# woochi.net
KiCad netlist of a schematic drawn in EAGLE
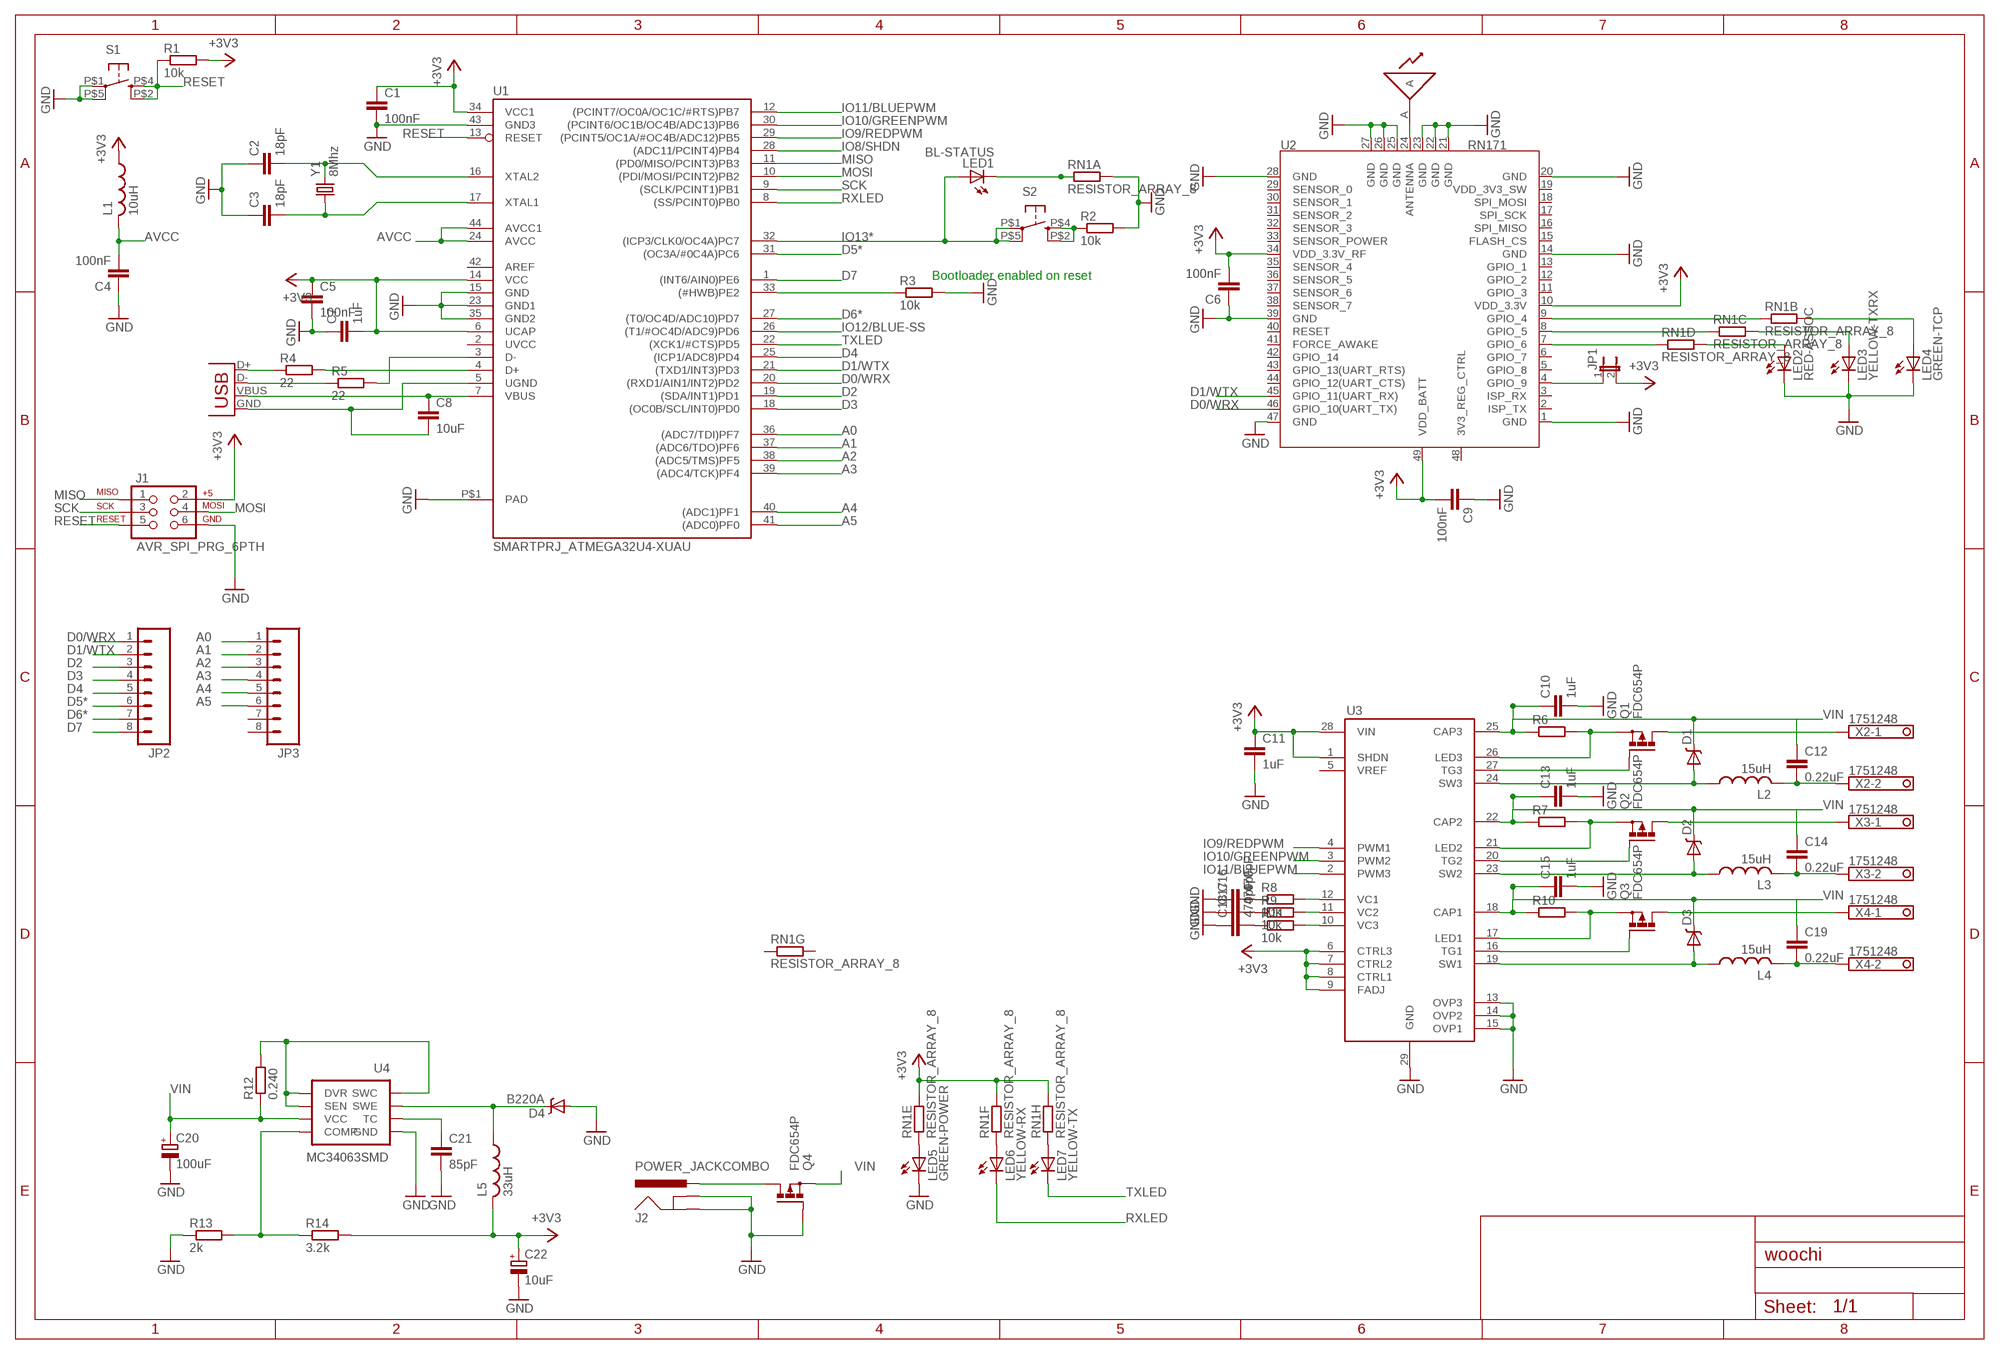
[diagram p0: schematic, sheet 1]

(export (version "E")
  (design (tool "Eeschema 10.0.6"))
  (components
    (comp (ref "A1")
      (value "ANTENNAWIRE")
      (footprint "eagle-import:ANTENNA-WIRE")
      (libsource (lib "eagle-import") (part "ANTENNAWIRE"))
    )
    (comp (ref "C1")
      (value "100nF")
      (footprint "eagle-import:C0603")
      (libsource (lib "eagle-import") (part "C-EUC0603"))
    )
    (comp (ref "C2")
      (value "18pF")
      (footprint "eagle-import:C0603")
      (libsource (lib "eagle-import") (part "C-EUC0603"))
    )
    (comp (ref "C3")
      (value "18pF")
      (footprint "eagle-import:C0603")
      (libsource (lib "eagle-import") (part "C-EUC0603"))
    )
    (comp (ref "C4")
      (value "100nF")
      (footprint "eagle-import:C0603")
      (libsource (lib "eagle-import") (part "C-EUC0603"))
    )
    (comp (ref "C5")
      (value "100nF")
      (footprint "eagle-import:C0603")
      (libsource (lib "eagle-import") (part "C-EUC0603"))
    )
    (comp (ref "C6")
      (value "100nF")
      (footprint "eagle-import:C0603")
      (libsource (lib "eagle-import") (part "C-EUC0603"))
    )
    (comp (ref "C7")
      (value "1uF")
      (footprint "eagle-import:C0603")
      (libsource (lib "eagle-import") (part "C-EUC0603"))
    )
    (comp (ref "C8")
      (value "10uF")
      (footprint "eagle-import:C0603")
      (libsource (lib "eagle-import") (part "C-EUC0603"))
    )
    (comp (ref "C9")
      (value "100nF")
      (footprint "eagle-import:C0603")
      (libsource (lib "eagle-import") (part "C-EUC0603"))
    )
    (comp (ref "C10")
      (value "1uF")
      (footprint "eagle-import:C0603")
      (libsource (lib "eagle-import") (part "C-EUC0603"))
    )
    (comp (ref "C11")
      (value "1uF")
      (footprint "eagle-import:C0603")
      (libsource (lib "eagle-import") (part "C-EUC0603"))
    )
    (comp (ref "C12")
      (value "0.22uF")
      (footprint "eagle-import:C0603")
      (libsource (lib "eagle-import") (part "C-EUC0603"))
    )
    (comp (ref "C13")
      (value "1uF")
      (footprint "eagle-import:C0603")
      (libsource (lib "eagle-import") (part "C-EUC0603"))
    )
    (comp (ref "C14")
      (value "0.22uF")
      (footprint "eagle-import:C0603")
      (libsource (lib "eagle-import") (part "C-EUC0603"))
    )
    (comp (ref "C15")
      (value "1uF")
      (footprint "eagle-import:C0603")
      (libsource (lib "eagle-import") (part "C-EUC0603"))
    )
    (comp (ref "C16")
      (value "470pF")
      (footprint "eagle-import:C0603")
      (libsource (lib "eagle-import") (part "C-EUC0603"))
    )
    (comp (ref "C17")
      (value "470pF")
      (footprint "eagle-import:C0603")
      (libsource (lib "eagle-import") (part "C-EUC0603"))
    )
    (comp (ref "C18")
      (value "470pF")
      (footprint "eagle-import:C0603")
      (libsource (lib "eagle-import") (part "C-EUC0603"))
    )
    (comp (ref "C19")
      (value "0.22uF")
      (footprint "eagle-import:C0603")
      (libsource (lib "eagle-import") (part "C-EUC0603"))
    )
    (comp (ref "C20")
      (value "100uF")
      (footprint "eagle-import:PANASONIC_D")
      (libsource (lib "eagle-import") (part "CPOL-EUD"))
    )
    (comp (ref "C21")
      (value "85pF")
      (footprint "eagle-import:C0603")
      (libsource (lib "eagle-import") (part "C-EUC0603"))
    )
    (comp (ref "C22")
      (value "10uF")
      (footprint "eagle-import:PANASONIC_C")
      (libsource (lib "eagle-import") (part "CPOL-EUC"))
    )
    (comp (ref "D1")
      (value "DIODE-SCHOTTKYBIGPAD")
      (footprint "eagle-import:SMA-DIODE-BIG")
      (libsource (lib "eagle-import") (part "DIODE-SCHOTTKYBIGPAD"))
    )
    (comp (ref "D2")
      (value "DIODE-SCHOTTKYBIGPAD")
      (footprint "eagle-import:SMA-DIODE-BIG")
      (libsource (lib "eagle-import") (part "DIODE-SCHOTTKYBIGPAD"))
    )
    (comp (ref "D3")
      (value "DIODE-SCHOTTKYBIGPAD")
      (footprint "eagle-import:SMA-DIODE-BIG")
      (libsource (lib "eagle-import") (part "DIODE-SCHOTTKYBIGPAD"))
    )
    (comp (ref "D4")
      (value "B220A")
      (footprint "eagle-import:SMA-DIODE-BIG")
      (libsource (lib "eagle-import") (part "DIODE-SCHOTTKYBIGPAD"))
    )
    (comp (ref "J1")
      (value "AVR_SPI_PRG_6PTH")
      (footprint "eagle-import:2X3")
      (libsource (lib "eagle-import") (part "AVR_SPI_PRG_6PTH"))
    )
    (comp (ref "J2")
      (value "POWER_JACKCOMBO")
      (footprint "eagle-import:POWER_JACK_COMBO")
      (libsource (lib "eagle-import") (part "POWER_JACKCOMBO"))
    )
    (comp (ref "JP1")
      (value "JUMPER-2PTH")
      (footprint "eagle-import:1X02")
      (libsource (lib "eagle-import") (part "JUMPER-2PTH"))
    )
    (comp (ref "JP2")
      (value "M081X08")
      (footprint "eagle-import:1X08")
      (libsource (lib "eagle-import") (part "M081X08"))
    )
    (comp (ref "JP3")
      (value "M081X08")
      (footprint "eagle-import:1X08")
      (libsource (lib "eagle-import") (part "M081X08"))
    )
    (comp (ref "L1")
      (value "10uH")
      (footprint "eagle-import:L0603")
      (libsource (lib "eagle-import") (part "L-USL0603"))
    )
    (comp (ref "L2")
      (value "15uH")
      (footprint "eagle-import:BOURNS-6045")
      (libsource (lib "eagle-import") (part "L-USBOURNS-6045"))
    )
    (comp (ref "L3")
      (value "15uH")
      (footprint "eagle-import:BOURNS-6045")
      (libsource (lib "eagle-import") (part "L-USBOURNS-6045"))
    )
    (comp (ref "L4")
      (value "15uH")
      (footprint "eagle-import:BOURNS-6045")
      (libsource (lib "eagle-import") (part "L-USBOURNS-6045"))
    )
    (comp (ref "L5")
      (value "33uH")
      (footprint "eagle-import:BOURNS-6045")
      (libsource (lib "eagle-import") (part "L-USBOURNS-6045"))
    )
    (comp (ref "LED1")
      (value "BL-STATUS")
      (footprint "eagle-import:SML0603")
      (libsource (lib "eagle-import") (part "LEDSML0603"))
    )
    (comp (ref "LED2")
      (value "RED-ASSOC")
      (footprint "eagle-import:SML0603")
      (libsource (lib "eagle-import") (part "LEDSML0603"))
    )
    (comp (ref "LED3")
      (value "YELLOW-TXRX")
      (footprint "eagle-import:SML0603")
      (libsource (lib "eagle-import") (part "LEDSML0603"))
    )
    (comp (ref "LED4")
      (value "GREEN-TCP")
      (footprint "eagle-import:SML0603")
      (libsource (lib "eagle-import") (part "LEDSML0603"))
    )
    (comp (ref "LED5")
      (value "GREEN-POWER")
      (footprint "eagle-import:SML0603")
      (libsource (lib "eagle-import") (part "LEDSML0603"))
    )
    (comp (ref "LED6")
      (value "YELLOW-RX")
      (footprint "eagle-import:SML0603")
      (libsource (lib "eagle-import") (part "LEDSML0603"))
    )
    (comp (ref "LED7")
      (value "YELLOW-TX")
      (footprint "eagle-import:SML0603")
      (libsource (lib "eagle-import") (part "LEDSML0603"))
    )
    (comp (ref "Q1")
      (value "FDC654P")
      (footprint "eagle-import:SUPERSOT6")
      (libsource (lib "eagle-import") (part "FDC654P"))
    )
    (comp (ref "Q2")
      (value "FDC654P")
      (footprint "eagle-import:SUPERSOT6")
      (libsource (lib "eagle-import") (part "FDC654P"))
    )
    (comp (ref "Q3")
      (value "FDC654P")
      (footprint "eagle-import:SUPERSOT6")
      (libsource (lib "eagle-import") (part "FDC654P"))
    )
    (comp (ref "Q4")
      (value "FDC654P")
      (footprint "eagle-import:SUPERSOT6")
      (libsource (lib "eagle-import") (part "FDC654P"))
    )
    (comp (ref "R1")
      (value "10k")
      (footprint "eagle-import:R0603")
      (libsource (lib "eagle-import") (part "R-EU_R0603"))
    )
    (comp (ref "R2")
      (value "10k")
      (footprint "eagle-import:R0603")
      (libsource (lib "eagle-import") (part "resistor_R-EU_R0603"))
    )
    (comp (ref "R3")
      (value "10k")
      (footprint "eagle-import:R0603")
      (libsource (lib "eagle-import") (part "resistor_R-EU_R0603"))
    )
    (comp (ref "R4")
      (value "22")
      (footprint "eagle-import:R0603")
      (libsource (lib "eagle-import") (part "R-EU_R0603"))
    )
    (comp (ref "R5")
      (value "22")
      (footprint "eagle-import:R0603")
      (libsource (lib "eagle-import") (part "R-EU_R0603"))
    )
    (comp (ref "R6")
      (value "R-EU_R0603")
      (footprint "eagle-import:R0603")
      (libsource (lib "eagle-import") (part "R-EU_R0603"))
    )
    (comp (ref "R7")
      (value "R-EU_R0603")
      (footprint "eagle-import:R0603")
      (libsource (lib "eagle-import") (part "R-EU_R0603"))
    )
    (comp (ref "R8")
      (value "10k")
      (footprint "eagle-import:R0603")
      (libsource (lib "eagle-import") (part "R-EU_R0603"))
    )
    (comp (ref "R9")
      (value "10k")
      (footprint "eagle-import:R0603")
      (libsource (lib "eagle-import") (part "R-EU_R0603"))
    )
    (comp (ref "R10")
      (value "R-EU_R0603")
      (footprint "eagle-import:R0603")
      (libsource (lib "eagle-import") (part "R-EU_R0603"))
    )
    (comp (ref "R11")
      (value "10k")
      (footprint "eagle-import:R0603")
      (libsource (lib "eagle-import") (part "R-EU_R0603"))
    )
    (comp (ref "R12")
      (value "0.240")
      (footprint "eagle-import:R0603")
      (libsource (lib "eagle-import") (part "R-EU_R0603"))
    )
    (comp (ref "R13")
      (value "2k")
      (footprint "eagle-import:R0603")
      (libsource (lib "eagle-import") (part "R-EU_R0603"))
    )
    (comp (ref "R14")
      (value "3.2k")
      (footprint "eagle-import:R0603")
      (libsource (lib "eagle-import") (part "R-EU_R0603"))
    )
    (comp (ref "RN1")
      (value "RESISTOR_ARRAY_8")
      (footprint "eagle-import:CAT16-F8_CAT16-J8")
      (libsource (lib "eagle-import") (part "RESISTOR_ARRAY_8"))
    )
    (comp (ref "S1")
      (value "TAC_SWITCH")
      (footprint "eagle-import:CK-KMS_PEGS")
      (libsource (lib "eagle-import") (part "TAC_SWITCH"))
    )
    (comp (ref "S2")
      (value "TAC_SWITCH")
      (footprint "eagle-import:CK-KMS_PEGS")
      (libsource (lib "eagle-import") (part "TAC_SWITCH"))
    )
    (comp (ref "U1")
      (value "SMARTPRJ_ATMEGA32U4-XUAU")
      (footprint "eagle-import:SMARTPRJ_TQFP44-PAD")
      (libsource (lib "eagle-import") (part "SMARTPRJ_ATMEGA32U4-XUAU"))
    )
    (comp (ref "U2")
      (value "RN171")
      (footprint "eagle-import:MODULE_49P-1.27-26.67X17.78")
      (libsource (lib "eagle-import") (part "MODULE_WIFI-RN-171"))
    )
    (comp (ref "U3")
      (value "LT3496")
      (footprint "eagle-import:SSOP28_THERMAL")
      (libsource (lib "eagle-import") (part "LT3496"))
    )
    (comp (ref "U4")
      (value "MC34063SMD")
      (footprint "eagle-import:SO08")
      (libsource (lib "eagle-import") (part "MC34063SMD"))
    )
    (comp (ref "X1")
      (value "USB-MICROB")
      (footprint "eagle-import:USB-MICROB")
      (libsource (lib "eagle-import") (part "USB-MICROB"))
    )
    (comp (ref "X2")
      (value "1751248")
      (footprint "eagle-import:1751248")
      (libsource (lib "eagle-import") (part "1751248"))
    )
    (comp (ref "X3")
      (value "1751248")
      (footprint "eagle-import:1751248")
      (libsource (lib "eagle-import") (part "1751248"))
    )
    (comp (ref "X4")
      (value "1751248")
      (footprint "eagle-import:1751248")
      (libsource (lib "eagle-import") (part "1751248"))
    )
    (comp (ref "Y1")
      (value "8Mhz")
      (footprint "eagle-import:HC49UP")
      (libsource (lib "eagle-import") (part "CRYSTALSMD"))
    )
  )
  (nets
    (net (code "1") (name "+3V3") (class "Default")
      (node (ref "C1") (pin "1") (pinfunction "1_1") (pintype "passive"))
      (node (ref "C11") (pin "1") (pinfunction "1_1") (pintype "passive"))
      (node (ref "C22") (pin "+") (pinfunction "+_+") (pintype "passive"))
      (node (ref "C5") (pin "1") (pinfunction "1_1") (pintype "passive"))
      (node (ref "C6") (pin "2") (pinfunction "2_2") (pintype "passive"))
      (node (ref "C7") (pin "2") (pinfunction "2_2") (pintype "passive"))
      (node (ref "C9") (pin "2") (pinfunction "2_2") (pintype "passive"))
      (node (ref "J1") (pin "2") (pinfunction "2_2") (pintype "passive"))
      (node (ref "JP1") (pin "2") (pinfunction "2_2") (pintype "passive"))
      (node (ref "L1") (pin "1") (pinfunction "1_1") (pintype "passive"))
      (node (ref "L5") (pin "P$2") (pinfunction "2_P$2") (pintype "passive"))
      (node (ref "R1") (pin "2") (pinfunction "2_2") (pintype "passive"))
      (node (ref "R14") (pin "2") (pinfunction "2_2") (pintype "passive"))
      (node (ref "RN1") (pin "11") (pinfunction "2_11") (pintype "passive"))
      (node (ref "RN1") (pin "12") (pinfunction "2_12") (pintype "passive"))
      (node (ref "RN1") (pin "9") (pinfunction "2_9") (pintype "passive"))
      (node (ref "U1") (pin "14") (pinfunction "VCC_14") (pintype "power_in"))
      (node (ref "U1") (pin "34") (pinfunction "VCC1_34") (pintype "power_in"))
      (node (ref "U1") (pin "6") (pinfunction "UCAP_6") (pintype "passive"))
      (node (ref "U2") (pin "10") (pinfunction "VDD_3.3V_10") (pintype "power_in"))
      (node (ref "U2") (pin "34") (pinfunction "VDD_3.3V_RF_34") (pintype "power_in"))
      (node (ref "U2") (pin "49") (pinfunction "VDD_BATT_49") (pintype "bidirectional"))
      (node (ref "U3") (pin "1") (pinfunction "SHDN_1") (pintype "bidirectional"))
      (node (ref "U3") (pin "28") (pinfunction "VIN_28") (pintype "bidirectional"))
      (node (ref "U3") (pin "6") (pinfunction "CTRL3_6") (pintype "bidirectional"))
      (node (ref "U3") (pin "7") (pinfunction "CTRL2_7") (pintype "bidirectional"))
      (node (ref "U3") (pin "8") (pinfunction "CTRL1_8") (pintype "bidirectional"))
      (node (ref "U3") (pin "9") (pinfunction "FADJ_9") (pintype "bidirectional"))
    )
    (net (code "2") (name "/A0") (class "Default")
      (node (ref "JP3") (pin "1") (pinfunction "1_1") (pintype "passive"))
      (node (ref "U1") (pin "36") (pinfunction "(ADC7/TDI)PF7_36") (pintype "bidirectional"))
    )
    (net (code "3") (name "/A1") (class "Default")
      (node (ref "JP3") (pin "2") (pinfunction "2_2") (pintype "passive"))
      (node (ref "U1") (pin "37") (pinfunction "(ADC6/TDO)PF6_37") (pintype "bidirectional"))
    )
    (net (code "4") (name "/A2") (class "Default")
      (node (ref "JP3") (pin "3") (pinfunction "3_3") (pintype "passive"))
      (node (ref "U1") (pin "38") (pinfunction "(ADC5/TMS)PF5_38") (pintype "bidirectional"))
    )
    (net (code "5") (name "/A3") (class "Default")
      (node (ref "JP3") (pin "4") (pinfunction "4_4") (pintype "passive"))
      (node (ref "U1") (pin "39") (pinfunction "(ADC4/TCK)PF4_39") (pintype "bidirectional"))
    )
    (net (code "6") (name "/A4") (class "Default")
      (node (ref "JP3") (pin "5") (pinfunction "5_5") (pintype "passive"))
      (node (ref "U1") (pin "40") (pinfunction "(ADC1)PF1_40") (pintype "bidirectional"))
    )
    (net (code "7") (name "/A5") (class "Default")
      (node (ref "JP3") (pin "6") (pinfunction "6_6") (pintype "passive"))
      (node (ref "U1") (pin "41") (pinfunction "(ADC0)PF0_41") (pintype "bidirectional"))
    )
    (net (code "8") (name "/AREF") (class "Default")
      (node (ref "U1") (pin "42") (pinfunction "AREF_42") (pintype "power_in"))
    )
    (net (code "9") (name "/AVCC") (class "Default")
      (node (ref "C4") (pin "2") (pinfunction "2_2") (pintype "passive"))
      (node (ref "L1") (pin "2") (pinfunction "2_2") (pintype "passive"))
      (node (ref "U1") (pin "24") (pinfunction "AVCC_24") (pintype "power_in"))
      (node (ref "U1") (pin "44") (pinfunction "AVCC1_44") (pintype "power_in"))
    )
    (net (code "10") (name "/D0{slash}WRX") (class "Default")
      (node (ref "JP2") (pin "1") (pinfunction "1_1") (pintype "passive"))
      (node (ref "U1") (pin "20") (pinfunction "(RXD1/AIN1/INT2)PD2_20") (pintype "bidirectional"))
      (node (ref "U2") (pin "46") (pinfunction "GPIO_10(UART_TX)_46") (pintype "bidirectional"))
    )
    (net (code "11") (name "/D1{slash}WTX") (class "Default")
      (node (ref "JP2") (pin "2") (pinfunction "2_2") (pintype "passive"))
      (node (ref "U1") (pin "21") (pinfunction "(TXD1/INT3)PD3_21") (pintype "bidirectional"))
      (node (ref "U2") (pin "45") (pinfunction "GPIO_11(UART_RX)_45") (pintype "bidirectional"))
    )
    (net (code "12") (name "/D2") (class "Default")
      (node (ref "JP2") (pin "3") (pinfunction "3_3") (pintype "passive"))
      (node (ref "U1") (pin "19") (pinfunction "(SDA/INT1)PD1_19") (pintype "bidirectional"))
    )
    (net (code "13") (name "/D3") (class "Default")
      (node (ref "JP2") (pin "4") (pinfunction "4_4") (pintype "passive"))
      (node (ref "U1") (pin "18") (pinfunction "(OC0B/SCL/INT0)PD0_18") (pintype "bidirectional"))
    )
    (net (code "14") (name "/D4") (class "Default")
      (node (ref "JP2") (pin "5") (pinfunction "5_5") (pintype "passive"))
      (node (ref "U1") (pin "25") (pinfunction "(ICP1/ADC8)PD4_25") (pintype "bidirectional"))
    )
    (net (code "15") (name "/D5*") (class "Default")
      (node (ref "JP2") (pin "6") (pinfunction "6_6") (pintype "passive"))
      (node (ref "U1") (pin "31") (pinfunction "(OC3A/#0C4A)PC6_31") (pintype "bidirectional"))
    )
    (net (code "16") (name "/D6*") (class "Default")
      (node (ref "JP2") (pin "7") (pinfunction "7_7") (pintype "passive"))
      (node (ref "U1") (pin "27") (pinfunction "(T0/OC4D/ADC10)PD7_27") (pintype "bidirectional"))
    )
    (net (code "17") (name "/D7") (class "Default")
      (node (ref "JP2") (pin "8") (pinfunction "8_8") (pintype "passive"))
      (node (ref "U1") (pin "1") (pinfunction "(INT6/AIN0)PE6_1") (pintype "bidirectional"))
    )
    (net (code "18") (name "/IO8{slash}SHDN") (class "Default")
      (node (ref "U1") (pin "28") (pinfunction "(ADC11/PCINT4)PB4_28") (pintype "bidirectional"))
    )
    (net (code "19") (name "/IO9{slash}REDPWM") (class "Default")
      (node (ref "U1") (pin "29") (pinfunction "(PCINT5/OC1A/#OC4B/ADC12)PB5_29") (pintype "bidirectional"))
      (node (ref "U3") (pin "4") (pinfunction "PWM1_4") (pintype "bidirectional"))
    )
    (net (code "20") (name "/IO10{slash}GREENPWM") (class "Default")
      (node (ref "U1") (pin "30") (pinfunction "(PCINT6/OC1B/OC4B/ADC13)PB6_30") (pintype "bidirectional"))
      (node (ref "U3") (pin "3") (pinfunction "PWM2_3") (pintype "bidirectional"))
    )
    (net (code "21") (name "/IO11{slash}BLUEPWM") (class "Default")
      (node (ref "U1") (pin "12") (pinfunction "(PCINT7/OC0A/OC1C/#RTS)PB7_12") (pintype "bidirectional"))
      (node (ref "U3") (pin "2") (pinfunction "PWM3_2") (pintype "bidirectional"))
    )
    (net (code "22") (name "/IO12{slash}BLUE-SS") (class "Default")
      (node (ref "U1") (pin "26") (pinfunction "(T1/#OC4D/ADC9)PD6_26") (pintype "bidirectional"))
    )
    (net (code "23") (name "/IO13*") (class "Default")
      (node (ref "LED1") (pin "A") (pinfunction "A_A") (pintype "passive"))
      (node (ref "S2") (pin "P$1") (pinfunction "1_P$1") (pintype "passive"))
      (node (ref "S2") (pin "P$5") (pinfunction "2_P$5") (pintype "passive"))
      (node (ref "U1") (pin "32") (pinfunction "(ICP3/CLK0/OC4A)PC7_32") (pintype "bidirectional"))
    )
    (net (code "24") (name "/MISO") (class "Default")
      (node (ref "J1") (pin "1") (pinfunction "1_1") (pintype "passive"))
      (node (ref "U1") (pin "11") (pinfunction "(PD0/MISO/PCINT3)PB3_11") (pintype "bidirectional"))
    )
    (net (code "25") (name "/MOSI") (class "Default")
      (node (ref "J1") (pin "4") (pinfunction "4_4") (pintype "passive"))
      (node (ref "U1") (pin "10") (pinfunction "(PDI/MOSI/PCINT2)PB2_10") (pintype "bidirectional"))
    )
    (net (code "26") (name "/RESET") (class "Default")
      (node (ref "R1") (pin "1") (pinfunction "1_1") (pintype "passive"))
      (node (ref "S1") (pin "P$2") (pinfunction "4_P$2") (pintype "passive"))
      (node (ref "S1") (pin "P$4") (pinfunction "3_P$4") (pintype "passive"))
      (node (ref "U1") (pin "13") (pinfunction "RESET_13") (pintype "input"))
    )
    (net (code "27") (name "/RXLED") (class "Default")
      (node (ref "LED6") (pin "C") (pinfunction "C_C") (pintype "passive"))
      (node (ref "U1") (pin "8") (pinfunction "(SS/PCINT0)PB0_8") (pintype "bidirectional"))
    )
    (net (code "28") (name "/SCK") (class "Default")
      (node (ref "J1") (pin "3") (pinfunction "3_3") (pintype "passive"))
      (node (ref "U1") (pin "9") (pinfunction "(SCLK/PCINT1)PB1_9") (pintype "bidirectional"))
    )
    (net (code "29") (name "/TXLED") (class "Default")
      (node (ref "LED7") (pin "C") (pinfunction "C_C") (pintype "passive"))
      (node (ref "U1") (pin "22") (pinfunction "(XCK1/#CTS)PD5_22") (pintype "bidirectional"))
    )
    (net (code "30") (name "/UVCC") (class "Default")
      (node (ref "U1") (pin "2") (pinfunction "UVCC_2") (pintype "power_in"))
    )
    (net (code "31") (name "/VIN") (class "Default")
      (node (ref "C10") (pin "1") (pinfunction "1_1") (pintype "passive"))
      (node (ref "C12") (pin "1") (pinfunction "1_1") (pintype "passive"))
      (node (ref "C13") (pin "1") (pinfunction "1_1") (pintype "passive"))
      (node (ref "C14") (pin "1") (pinfunction "1_1") (pintype "passive"))
      (node (ref "C15") (pin "1") (pinfunction "1_1") (pintype "passive"))
      (node (ref "C19") (pin "1") (pinfunction "1_1") (pintype "passive"))
      (node (ref "C20") (pin "+") (pinfunction "+_+") (pintype "passive"))
      (node (ref "D1") (pin "C") (pinfunction "C_C") (pintype "passive"))
      (node (ref "D2") (pin "C") (pinfunction "C_C") (pintype "passive"))
      (node (ref "D3") (pin "C") (pinfunction "C_C") (pintype "passive"))
      (node (ref "Q4") (pin "P$4") (pinfunction "S_P$4") (pintype "passive"))
      (node (ref "R10") (pin "1") (pinfunction "1_1") (pintype "passive"))
      (node (ref "R12") (pin "1") (pinfunction "1_1") (pintype "passive"))
      (node (ref "R6") (pin "1") (pinfunction "1_1") (pintype "passive"))
      (node (ref "R7") (pin "1") (pinfunction "1_1") (pintype "passive"))
      (node (ref "U3") (pin "18") (pinfunction "CAP1_18") (pintype "bidirectional"))
      (node (ref "U3") (pin "22") (pinfunction "CAP2_22") (pintype "bidirectional"))
      (node (ref "U3") (pin "25") (pinfunction "CAP3_25") (pintype "bidirectional"))
      (node (ref "U4") (pin "6") (pinfunction "VCC_6") (pintype "bidirectional"))
    )
    (net (code "32") (name "GND") (class "Default")
      (node (ref "C1") (pin "2") (pinfunction "2_2") (pintype "passive"))
      (node (ref "C10") (pin "2") (pinfunction "2_2") (pintype "passive"))
      (node (ref "C11") (pin "2") (pinfunction "2_2") (pintype "passive"))
      (node (ref "C13") (pin "2") (pinfunction "2_2") (pintype "passive"))
      (node (ref "C15") (pin "2") (pinfunction "2_2") (pintype "passive"))
      (node (ref "C16") (pin "1") (pinfunction "1_1") (pintype "passive"))
      (node (ref "C17") (pin "1") (pinfunction "1_1") (pintype "passive"))
      (node (ref "C18") (pin "1") (pinfunction "1_1") (pintype "passive"))
      (node (ref "C2") (pin "1") (pinfunction "1_1") (pintype "passive"))
      (node (ref "C20") (pin "-") (pinfunction "-_-") (pintype "passive"))
      (node (ref "C21") (pin "2") (pinfunction "2_2") (pintype "passive"))
      (node (ref "C22") (pin "-") (pinfunction "-_-") (pintype "passive"))
      (node (ref "C3") (pin "1") (pinfunction "1_1") (pintype "passive"))
      (node (ref "C4") (pin "1") (pinfunction "1_1") (pintype "passive"))
      (node (ref "C5") (pin "2") (pinfunction "2_2") (pintype "passive"))
      (node (ref "C6") (pin "1") (pinfunction "1_1") (pintype "passive"))
      (node (ref "C7") (pin "1") (pinfunction "1_1") (pintype "passive"))
      (node (ref "C9") (pin "1") (pinfunction "1_1") (pintype "passive"))
      (node (ref "D4") (pin "A") (pinfunction "A_A") (pintype "passive"))
      (node (ref "J1") (pin "6") (pinfunction "6_6") (pintype "passive"))
      (node (ref "J2") (pin "GND") (pinfunction "GNDBREAK_GND") (pintype "bidirectional"))
      (node (ref "J2") (pin "GND@1") (pinfunction "GND_GND@1") (pintype "bidirectional"))
      (node (ref "LED2") (pin "C") (pinfunction "C_C") (pintype "passive"))
      (node (ref "LED3") (pin "C") (pinfunction "C_C") (pintype "passive"))
      (node (ref "LED4") (pin "C") (pinfunction "C_C") (pintype "passive"))
      (node (ref "LED5") (pin "C") (pinfunction "C_C") (pintype "passive"))
      (node (ref "Q4") (pin "P$3") (pinfunction "G_P$3") (pintype "passive"))
      (node (ref "R13") (pin "1") (pinfunction "1_1") (pintype "passive"))
      (node (ref "R2") (pin "2") (pinfunction "2_2") (pintype "passive"))
      (node (ref "R3") (pin "2") (pinfunction "2_2") (pintype "passive"))
      (node (ref "RN1") (pin "16") (pinfunction "2_16") (pintype "passive"))
      (node (ref "S1") (pin "P$1") (pinfunction "1_P$1") (pintype "passive"))
      (node (ref "S1") (pin "P$5") (pinfunction "2_P$5") (pintype "passive"))
      (node (ref "U1") (pin "15") (pinfunction "GND_15") (pintype "power_in"))
      (node (ref "U1") (pin "23") (pinfunction "GND1_23") (pintype "power_in"))
      (node (ref "U1") (pin "35") (pinfunction "GND2_35") (pintype "power_in"))
      (node (ref "U1") (pin "43") (pinfunction "GND3_43") (pintype "power_in"))
      (node (ref "U1") (pin "P$1") (pinfunction "PAD_P$1") (pintype "power_in"))
      (node (ref "U2") (pin "1") (pinfunction "GND_1") (pintype "power_in"))
      (node (ref "U2") (pin "14") (pinfunction "GND_14") (pintype "power_in"))
      (node (ref "U2") (pin "20") (pinfunction "GND_20") (pintype "power_in"))
      (node (ref "U2") (pin "21") (pinfunction "GND_21") (pintype "power_in"))
      (node (ref "U2") (pin "22") (pinfunction "GND_22") (pintype "power_in"))
      (node (ref "U2") (pin "23") (pinfunction "GND_23") (pintype "power_in"))
      (node (ref "U2") (pin "25") (pinfunction "GND_25") (pintype "power_in"))
      (node (ref "U2") (pin "26") (pinfunction "GND_26") (pintype "power_in"))
      (node (ref "U2") (pin "27") (pinfunction "GND_27") (pintype "power_in"))
      (node (ref "U2") (pin "28") (pinfunction "GND_28") (pintype "power_in"))
      (node (ref "U2") (pin "39") (pinfunction "GND_39") (pintype "power_in"))
      (node (ref "U2") (pin "47") (pinfunction "GND_47") (pintype "power_in"))
      (node (ref "U3") (pin "13") (pinfunction "OVP3_13") (pintype "bidirectional"))
      (node (ref "U3") (pin "14") (pinfunction "OVP2_14") (pintype "bidirectional"))
      (node (ref "U3") (pin "15") (pinfunction "OVP1_15") (pintype "bidirectional"))
      (node (ref "U3") (pin "29") (pinfunction "GND_29") (pintype "bidirectional"))
      (node (ref "U4") (pin "4") (pinfunction "GND_4") (pintype "bidirectional"))
    )
    (net (code "33") (name "Net-(C16-Pad2)") (class "Default")
      (node (ref "C16") (pin "2") (pinfunction "2_2") (pintype "passive"))
      (node (ref "R8") (pin "1") (pinfunction "1_1") (pintype "passive"))
    )
    (net (code "34") (name "Net-(C17-Pad2)") (class "Default")
      (node (ref "C17") (pin "2") (pinfunction "2_2") (pintype "passive"))
      (node (ref "R9") (pin "1") (pinfunction "1_1") (pintype "passive"))
    )
    (net (code "35") (name "Net-(C18-Pad2)") (class "Default")
      (node (ref "C18") (pin "2") (pinfunction "2_2") (pintype "passive"))
      (node (ref "R11") (pin "1") (pinfunction "1_1") (pintype "passive"))
    )
    (net (code "36") (name "Net-(J2-PWR)") (class "Default")
      (node (ref "J2") (pin "POWER") (pinfunction "PWR_POWER") (pintype "bidirectional"))
      (node (ref "Q4") (pin "P$1") (pinfunction "D_P$1") (pintype "passive"))
      (node (ref "Q4") (pin "P$2") (pinfunction "D_P$2") (pintype "passive"))
      (node (ref "Q4") (pin "P$5") (pinfunction "D_P$5") (pintype "passive"))
      (node (ref "Q4") (pin "P$6") (pinfunction "D_P$6") (pintype "passive"))
    )
    (net (code "37") (name "Net-(L2-1)") (class "Default")
      (node (ref "D1") (pin "A") (pinfunction "A_A") (pintype "passive"))
      (node (ref "L2") (pin "P$1") (pinfunction "1_P$1") (pintype "passive"))
      (node (ref "U3") (pin "24") (pinfunction "SW3_24") (pintype "bidirectional"))
    )
    (net (code "38") (name "Net-(L2-2)") (class "Default")
      (node (ref "C12") (pin "2") (pinfunction "2_2") (pintype "passive"))
      (node (ref "L2") (pin "P$2") (pinfunction "2_P$2") (pintype "passive"))
      (node (ref "X2") (pin "2") (pinfunction "K_2") (pintype "passive"))
    )
    (net (code "39") (name "Net-(L3-1)") (class "Default")
      (node (ref "D2") (pin "A") (pinfunction "A_A") (pintype "passive"))
      (node (ref "L3") (pin "P$1") (pinfunction "1_P$1") (pintype "passive"))
      (node (ref "U3") (pin "23") (pinfunction "SW2_23") (pintype "bidirectional"))
    )
    (net (code "40") (name "Net-(L3-2)") (class "Default")
      (node (ref "C14") (pin "2") (pinfunction "2_2") (pintype "passive"))
      (node (ref "L3") (pin "P$2") (pinfunction "2_P$2") (pintype "passive"))
      (node (ref "X3") (pin "2") (pinfunction "K_2") (pintype "passive"))
    )
    (net (code "41") (name "Net-(L4-1)") (class "Default")
      (node (ref "D3") (pin "A") (pinfunction "A_A") (pintype "passive"))
      (node (ref "L4") (pin "P$1") (pinfunction "1_P$1") (pintype "passive"))
      (node (ref "U3") (pin "19") (pinfunction "SW1_19") (pintype "bidirectional"))
    )
    (net (code "42") (name "Net-(L4-2)") (class "Default")
      (node (ref "C19") (pin "2") (pinfunction "2_2") (pintype "passive"))
      (node (ref "L4") (pin "P$2") (pinfunction "2_P$2") (pintype "passive"))
      (node (ref "X4") (pin "2") (pinfunction "K_2") (pintype "passive"))
    )
    (net (code "43") (name "Net-(L5-1)") (class "Default")
      (node (ref "D4") (pin "C") (pinfunction "C_C") (pintype "passive"))
      (node (ref "L5") (pin "P$1") (pinfunction "1_P$1") (pintype "passive"))
      (node (ref "U4") (pin "2") (pinfunction "SWE_2") (pintype "bidirectional"))
    )
    (net (code "44") (name "Net-(LED1-PadC)") (class "Default")
      (node (ref "LED1") (pin "C") (pinfunction "C_C") (pintype "passive"))
      (node (ref "RN1") (pin "1") (pinfunction "1_1") (pintype "passive"))
    )
    (net (code "45") (name "Net-(Q1-G)") (class "Default")
      (node (ref "Q1") (pin "P$3") (pinfunction "G_P$3") (pintype "passive"))
      (node (ref "U3") (pin "27") (pinfunction "TG3_27") (pintype "bidirectional"))
    )
    (net (code "46") (name "Net-(Q1-S)") (class "Default")
      (node (ref "Q1") (pin "P$4") (pinfunction "S_P$4") (pintype "passive"))
      (node (ref "R6") (pin "2") (pinfunction "2_2") (pintype "passive"))
      (node (ref "U3") (pin "26") (pinfunction "LED3_26") (pintype "bidirectional"))
    )
    (net (code "47") (name "Net-(Q2-G)") (class "Default")
      (node (ref "Q2") (pin "P$3") (pinfunction "G_P$3") (pintype "passive"))
      (node (ref "U3") (pin "20") (pinfunction "TG2_20") (pintype "bidirectional"))
    )
    (net (code "48") (name "Net-(Q2-S)") (class "Default")
      (node (ref "Q2") (pin "P$4") (pinfunction "S_P$4") (pintype "passive"))
      (node (ref "R7") (pin "2") (pinfunction "2_2") (pintype "passive"))
      (node (ref "U3") (pin "21") (pinfunction "LED2_21") (pintype "bidirectional"))
    )
    (net (code "49") (name "Net-(Q3-G)") (class "Default")
      (node (ref "Q3") (pin "P$3") (pinfunction "G_P$3") (pintype "passive"))
      (node (ref "U3") (pin "16") (pinfunction "TG1_16") (pintype "bidirectional"))
    )
    (net (code "50") (name "Net-(Q3-S)") (class "Default")
      (node (ref "Q3") (pin "P$4") (pinfunction "S_P$4") (pintype "passive"))
      (node (ref "R10") (pin "2") (pinfunction "2_2") (pintype "passive"))
      (node (ref "U3") (pin "17") (pinfunction "LED1_17") (pintype "bidirectional"))
    )
    (net (code "51") (name "Net-(R4-Pad1)") (class "Default")
      (node (ref "R4") (pin "1") (pinfunction "1_1") (pintype "passive"))
      (node (ref "X1") (pin "D+") (pinfunction "D+_D+") (pintype "bidirectional"))
    )
    (net (code "52") (name "Net-(R5-Pad1)") (class "Default")
      (node (ref "R5") (pin "1") (pinfunction "1_1") (pintype "passive"))
      (node (ref "X1") (pin "D-") (pinfunction "D-_D-") (pintype "bidirectional"))
    )
    (net (code "53") (name "Net-(RN1B-1)") (class "Default")
      (node (ref "RN1") (pin "2") (pinfunction "1_2") (pintype "passive"))
      (node (ref "U2") (pin "9") (pinfunction "GPIO_4_9") (pintype "bidirectional"))
    )
    (net (code "54") (name "Net-(RN1B-2)") (class "Default")
      (node (ref "LED4") (pin "A") (pinfunction "A_A") (pintype "passive"))
      (node (ref "RN1") (pin "15") (pinfunction "2_15") (pintype "passive"))
    )
    (net (code "55") (name "Net-(RN1C-1)") (class "Default")
      (node (ref "RN1") (pin "3") (pinfunction "1_3") (pintype "passive"))
      (node (ref "U2") (pin "8") (pinfunction "GPIO_5_8") (pintype "bidirectional"))
    )
    (net (code "56") (name "Net-(RN1C-2)") (class "Default")
      (node (ref "LED3") (pin "A") (pinfunction "A_A") (pintype "passive"))
      (node (ref "RN1") (pin "14") (pinfunction "2_14") (pintype "passive"))
    )
    (net (code "57") (name "Net-(RN1D-1)") (class "Default")
      (node (ref "RN1") (pin "4") (pinfunction "1_4") (pintype "passive"))
      (node (ref "U2") (pin "7") (pinfunction "GPIO_6_7") (pintype "bidirectional"))
    )
    (net (code "58") (name "Net-(RN1D-2)") (class "Default")
      (node (ref "LED2") (pin "A") (pinfunction "A_A") (pintype "passive"))
      (node (ref "RN1") (pin "13") (pinfunction "2_13") (pintype "passive"))
    )
    (net (code "59") (name "Net-(RN1E-1)") (class "Default")
      (node (ref "LED5") (pin "A") (pinfunction "A_A") (pintype "passive"))
      (node (ref "RN1") (pin "5") (pinfunction "1_5") (pintype "passive"))
    )
    (net (code "60") (name "Net-(RN1F-1)") (class "Default")
      (node (ref "LED6") (pin "A") (pinfunction "A_A") (pintype "passive"))
      (node (ref "RN1") (pin "6") (pinfunction "1_6") (pintype "passive"))
    )
    (net (code "61") (name "Net-(RN1H-1)") (class "Default")
      (node (ref "LED7") (pin "A") (pinfunction "A_A") (pintype "passive"))
      (node (ref "RN1") (pin "8") (pinfunction "1_8") (pintype "passive"))
    )
    (net (code "62") (name "Net-(S2-3)") (class "Default")
      (node (ref "R2") (pin "1") (pinfunction "1_1") (pintype "passive"))
      (node (ref "S2") (pin "P$2") (pinfunction "4_P$2") (pintype "passive"))
      (node (ref "S2") (pin "P$4") (pinfunction "3_P$4") (pintype "passive"))
    )
    (net (code "63") (name "Net-(U1-(#HWB)PE2)") (class "Default")
      (node (ref "R3") (pin "1") (pinfunction "1_1") (pintype "passive"))
      (node (ref "U1") (pin "33") (pinfunction "(#HWB)PE2_33") (pintype "bidirectional"))
    )
    (net (code "64") (name "Net-(U1-D+)") (class "Default")
      (node (ref "R4") (pin "2") (pinfunction "2_2") (pintype "passive"))
      (node (ref "U1") (pin "4") (pinfunction "D+_4") (pintype "bidirectional"))
    )
    (net (code "65") (name "Net-(U1-D-)") (class "Default")
      (node (ref "R5") (pin "2") (pinfunction "2_2") (pintype "passive"))
      (node (ref "U1") (pin "3") (pinfunction "D-_3") (pintype "bidirectional"))
    )
    (net (code "66") (name "Net-(U1-UGND)") (class "Default")
      (node (ref "C8") (pin "2") (pinfunction "2_2") (pintype "passive"))
      (node (ref "U1") (pin "5") (pinfunction "UGND_5") (pintype "power_in"))
      (node (ref "X1") (pin "GND") (pinfunction "GND_GND") (pintype "bidirectional"))
    )
    (net (code "67") (name "Net-(U1-VBUS)") (class "Default")
      (node (ref "C8") (pin "1") (pinfunction "1_1") (pintype "passive"))
      (node (ref "U1") (pin "7") (pinfunction "VBUS_7") (pintype "input"))
      (node (ref "X1") (pin "VBUS") (pinfunction "VBUS_VBUS") (pintype "bidirectional"))
    )
    (net (code "68") (name "Net-(U1-XTAL1)") (class "Default")
      (node (ref "C3") (pin "2") (pinfunction "2_2") (pintype "passive"))
      (node (ref "U1") (pin "17") (pinfunction "XTAL1_17") (pintype "bidirectional"))
      (node (ref "Y1") (pin "1") (pinfunction "1_1") (pintype "passive"))
    )
    (net (code "69") (name "Net-(U1-XTAL2)") (class "Default")
      (node (ref "C2") (pin "2") (pinfunction "2_2") (pintype "passive"))
      (node (ref "U1") (pin "16") (pinfunction "XTAL2_16") (pintype "bidirectional"))
      (node (ref "Y1") (pin "2") (pinfunction "2_2") (pintype "passive"))
    )
    (net (code "70") (name "Net-(U2-ANTENNA)") (class "Default")
      (node (ref "A1") (pin "A") (pinfunction "A_A") (pintype "bidirectional"))
      (node (ref "U2") (pin "24") (pinfunction "ANTENNA_24") (pintype "bidirectional"))
    )
    (net (code "71") (name "Net-(U2-GPIO_9)") (class "Default")
      (node (ref "JP1") (pin "1") (pinfunction "1_1") (pintype "passive"))
      (node (ref "U2") (pin "4") (pinfunction "GPIO_9_4") (pintype "bidirectional"))
    )
    (net (code "72") (name "Net-(U3-VC1)") (class "Default")
      (node (ref "R8") (pin "2") (pinfunction "2_2") (pintype "passive"))
      (node (ref "U3") (pin "12") (pinfunction "VC1_12") (pintype "bidirectional"))
    )
    (net (code "73") (name "Net-(U3-VC2)") (class "Default")
      (node (ref "R9") (pin "2") (pinfunction "2_2") (pintype "passive"))
      (node (ref "U3") (pin "11") (pinfunction "VC2_11") (pintype "bidirectional"))
    )
    (net (code "74") (name "Net-(U3-VC3)") (class "Default")
      (node (ref "R11") (pin "2") (pinfunction "2_2") (pintype "passive"))
      (node (ref "U3") (pin "10") (pinfunction "VC3_10") (pintype "bidirectional"))
    )
    (net (code "75") (name "Net-(U4-COMP)") (class "Default")
      (node (ref "R13") (pin "2") (pinfunction "2_2") (pintype "passive"))
      (node (ref "R14") (pin "1") (pinfunction "1_1") (pintype "passive"))
      (node (ref "U4") (pin "5") (pinfunction "COMP_5") (pintype "bidirectional"))
    )
    (net (code "76") (name "Net-(U4-DVR)") (class "Default")
      (node (ref "R12") (pin "2") (pinfunction "2_2") (pintype "passive"))
      (node (ref "U4") (pin "1") (pinfunction "SWC_1") (pintype "bidirectional"))
      (node (ref "U4") (pin "7") (pinfunction "SEN_7") (pintype "bidirectional"))
      (node (ref "U4") (pin "8") (pinfunction "DVR_8") (pintype "bidirectional"))
    )
    (net (code "77") (name "Net-(U4-TC)") (class "Default")
      (node (ref "C21") (pin "1") (pinfunction "1_1") (pintype "passive"))
      (node (ref "U4") (pin "3") (pinfunction "TC_3") (pintype "bidirectional"))
    )
    (net (code "78") (name "Net-(X2A-K)") (class "Default")
      (node (ref "Q1") (pin "P$1") (pinfunction "D_P$1") (pintype "passive"))
      (node (ref "Q1") (pin "P$2") (pinfunction "D_P$2") (pintype "passive"))
      (node (ref "Q1") (pin "P$5") (pinfunction "D_P$5") (pintype "passive"))
      (node (ref "Q1") (pin "P$6") (pinfunction "D_P$6") (pintype "passive"))
      (node (ref "X2") (pin "1") (pinfunction "K_1") (pintype "passive"))
    )
    (net (code "79") (name "Net-(X3A-K)") (class "Default")
      (node (ref "Q2") (pin "P$1") (pinfunction "D_P$1") (pintype "passive"))
      (node (ref "Q2") (pin "P$2") (pinfunction "D_P$2") (pintype "passive"))
      (node (ref "Q2") (pin "P$5") (pinfunction "D_P$5") (pintype "passive"))
      (node (ref "Q2") (pin "P$6") (pinfunction "D_P$6") (pintype "passive"))
      (node (ref "X3") (pin "1") (pinfunction "K_1") (pintype "passive"))
    )
    (net (code "80") (name "Net-(X4A-K)") (class "Default")
      (node (ref "Q3") (pin "P$1") (pinfunction "D_P$1") (pintype "passive"))
      (node (ref "Q3") (pin "P$2") (pinfunction "D_P$2") (pintype "passive"))
      (node (ref "Q3") (pin "P$5") (pinfunction "D_P$5") (pintype "passive"))
      (node (ref "Q3") (pin "P$6") (pinfunction "D_P$6") (pintype "passive"))
      (node (ref "X4") (pin "1") (pinfunction "K_1") (pintype "passive"))
    )
    (net (code "81") (name "unconnected-(J1-Pad5)") (class "Default")
      (node (ref "J1") (pin "5") (pinfunction "5_5") (pintype "passive"))
    )
    (net (code "82") (name "unconnected-(JP3-Pad7)") (class "Default")
      (node (ref "JP3") (pin "7") (pinfunction "7_7") (pintype "passive"))
    )
    (net (code "83") (name "unconnected-(JP3-Pad8)") (class "Default")
      (node (ref "JP3") (pin "8") (pinfunction "8_8") (pintype "passive"))
    )
    (net (code "84") (name "unconnected-(RN1G-1-Pad7)") (class "Default")
      (node (ref "RN1") (pin "7") (pinfunction "1_7") (pintype "passive"))
    )
    (net (code "85") (name "unconnected-(RN1G-2-Pad10)") (class "Default")
      (node (ref "RN1") (pin "10") (pinfunction "2_10") (pintype "passive"))
    )
    (net (code "86") (name "unconnected-(U2-3V3_REG_CTRL-Pad48)") (class "Default")
      (node (ref "U2") (pin "48") (pinfunction "3V3_REG_CTRL_48") (pintype "input"))
    )
    (net (code "87") (name "unconnected-(U2-FLASH_CS-Pad15)") (class "Default")
      (node (ref "U2") (pin "15") (pinfunction "FLASH_CS_15") (pintype "bidirectional"))
    )
    (net (code "88") (name "unconnected-(U2-FORCE_AWAKE-Pad41)") (class "Default")
      (node (ref "U2") (pin "41") (pinfunction "FORCE_AWAKE_41") (pintype "bidirectional"))
    )
    (net (code "89") (name "unconnected-(U2-GPIO_1-Pad13)") (class "Default")
      (node (ref "U2") (pin "13") (pinfunction "GPIO_1_13") (pintype "bidirectional"))
    )
    (net (code "90") (name "unconnected-(U2-GPIO_2-Pad12)") (class "Default")
      (node (ref "U2") (pin "12") (pinfunction "GPIO_2_12") (pintype "bidirectional"))
    )
    (net (code "91") (name "unconnected-(U2-GPIO_3-Pad11)") (class "Default")
      (node (ref "U2") (pin "11") (pinfunction "GPIO_3_11") (pintype "bidirectional"))
    )
    (net (code "92") (name "unconnected-(U2-GPIO_7-Pad6)") (class "Default")
      (node (ref "U2") (pin "6") (pinfunction "GPIO_7_6") (pintype "bidirectional"))
    )
    (net (code "93") (name "unconnected-(U2-GPIO_8-Pad5)") (class "Default")
      (node (ref "U2") (pin "5") (pinfunction "GPIO_8_5") (pintype "bidirectional"))
    )
    (net (code "94") (name "unconnected-(U2-GPIO_12(UART_CTS)-Pad44)") (class "Default")
      (node (ref "U2") (pin "44") (pinfunction "GPIO_12(UART_CTS)_44") (pintype "bidirectional"))
    )
    (net (code "95") (name "unconnected-(U2-GPIO_13(UART_RTS)-Pad43)") (class "Default")
      (node (ref "U2") (pin "43") (pinfunction "GPIO_13(UART_RTS)_43") (pintype "bidirectional"))
    )
    (net (code "96") (name "unconnected-(U2-GPIO_14-Pad42)") (class "Default")
      (node (ref "U2") (pin "42") (pinfunction "GPIO_14_42") (pintype "bidirectional"))
    )
    (net (code "97") (name "unconnected-(U2-ISP_RX-Pad3)") (class "Default")
      (node (ref "U2") (pin "3") (pinfunction "ISP_RX_3") (pintype "bidirectional"))
    )
    (net (code "98") (name "unconnected-(U2-ISP_TX-Pad2)") (class "Default")
      (node (ref "U2") (pin "2") (pinfunction "ISP_TX_2") (pintype "bidirectional"))
    )
    (net (code "99") (name "unconnected-(U2-RESET-Pad40)") (class "Default")
      (node (ref "U2") (pin "40") (pinfunction "RESET_40") (pintype "input"))
    )
    (net (code "100") (name "unconnected-(U2-SENSOR_0-Pad29)") (class "Default")
      (node (ref "U2") (pin "29") (pinfunction "SENSOR_0_29") (pintype "input"))
    )
    (net (code "101") (name "unconnected-(U2-SENSOR_1-Pad30)") (class "Default")
      (node (ref "U2") (pin "30") (pinfunction "SENSOR_1_30") (pintype "input"))
    )
    (net (code "102") (name "unconnected-(U2-SENSOR_2-Pad31)") (class "Default")
      (node (ref "U2") (pin "31") (pinfunction "SENSOR_2_31") (pintype "input"))
    )
    (net (code "103") (name "unconnected-(U2-SENSOR_3-Pad32)") (class "Default")
      (node (ref "U2") (pin "32") (pinfunction "SENSOR_3_32") (pintype "input"))
    )
    (net (code "104") (name "unconnected-(U2-SENSOR_4-Pad35)") (class "Default")
      (node (ref "U2") (pin "35") (pinfunction "SENSOR_4_35") (pintype "input"))
    )
    (net (code "105") (name "unconnected-(U2-SENSOR_5-Pad36)") (class "Default")
      (node (ref "U2") (pin "36") (pinfunction "SENSOR_5_36") (pintype "input"))
    )
    (net (code "106") (name "unconnected-(U2-SENSOR_6-Pad37)") (class "Default")
      (node (ref "U2") (pin "37") (pinfunction "SENSOR_6_37") (pintype "input"))
    )
    (net (code "107") (name "unconnected-(U2-SENSOR_7-Pad38)") (class "Default")
      (node (ref "U2") (pin "38") (pinfunction "SENSOR_7_38") (pintype "input"))
    )
    (net (code "108") (name "unconnected-(U2-SENSOR_POWER-Pad33)") (class "Default")
      (node (ref "U2") (pin "33") (pinfunction "SENSOR_POWER_33") (pintype "output"))
    )
    (net (code "109") (name "unconnected-(U2-SPI_MISO-Pad16)") (class "Default")
      (node (ref "U2") (pin "16") (pinfunction "SPI_MISO_16") (pintype "bidirectional"))
    )
    (net (code "110") (name "unconnected-(U2-SPI_MOSI-Pad18)") (class "Default")
      (node (ref "U2") (pin "18") (pinfunction "SPI_MOSI_18") (pintype "bidirectional"))
    )
    (net (code "111") (name "unconnected-(U2-SPI_SCK-Pad17)") (class "Default")
      (node (ref "U2") (pin "17") (pinfunction "SPI_SCK_17") (pintype "bidirectional"))
    )
    (net (code "112") (name "unconnected-(U2-VDD_3V3_SW-Pad19)") (class "Default")
      (node (ref "U2") (pin "19") (pinfunction "VDD_3V3_SW_19") (pintype "bidirectional"))
    )
    (net (code "113") (name "unconnected-(U3-VREF-Pad5)") (class "Default")
      (node (ref "U3") (pin "5") (pinfunction "VREF_5") (pintype "bidirectional"))
    )
  )
)
